# zif_socket.net
KiCad netlist of a schematic drawn in EAGLE
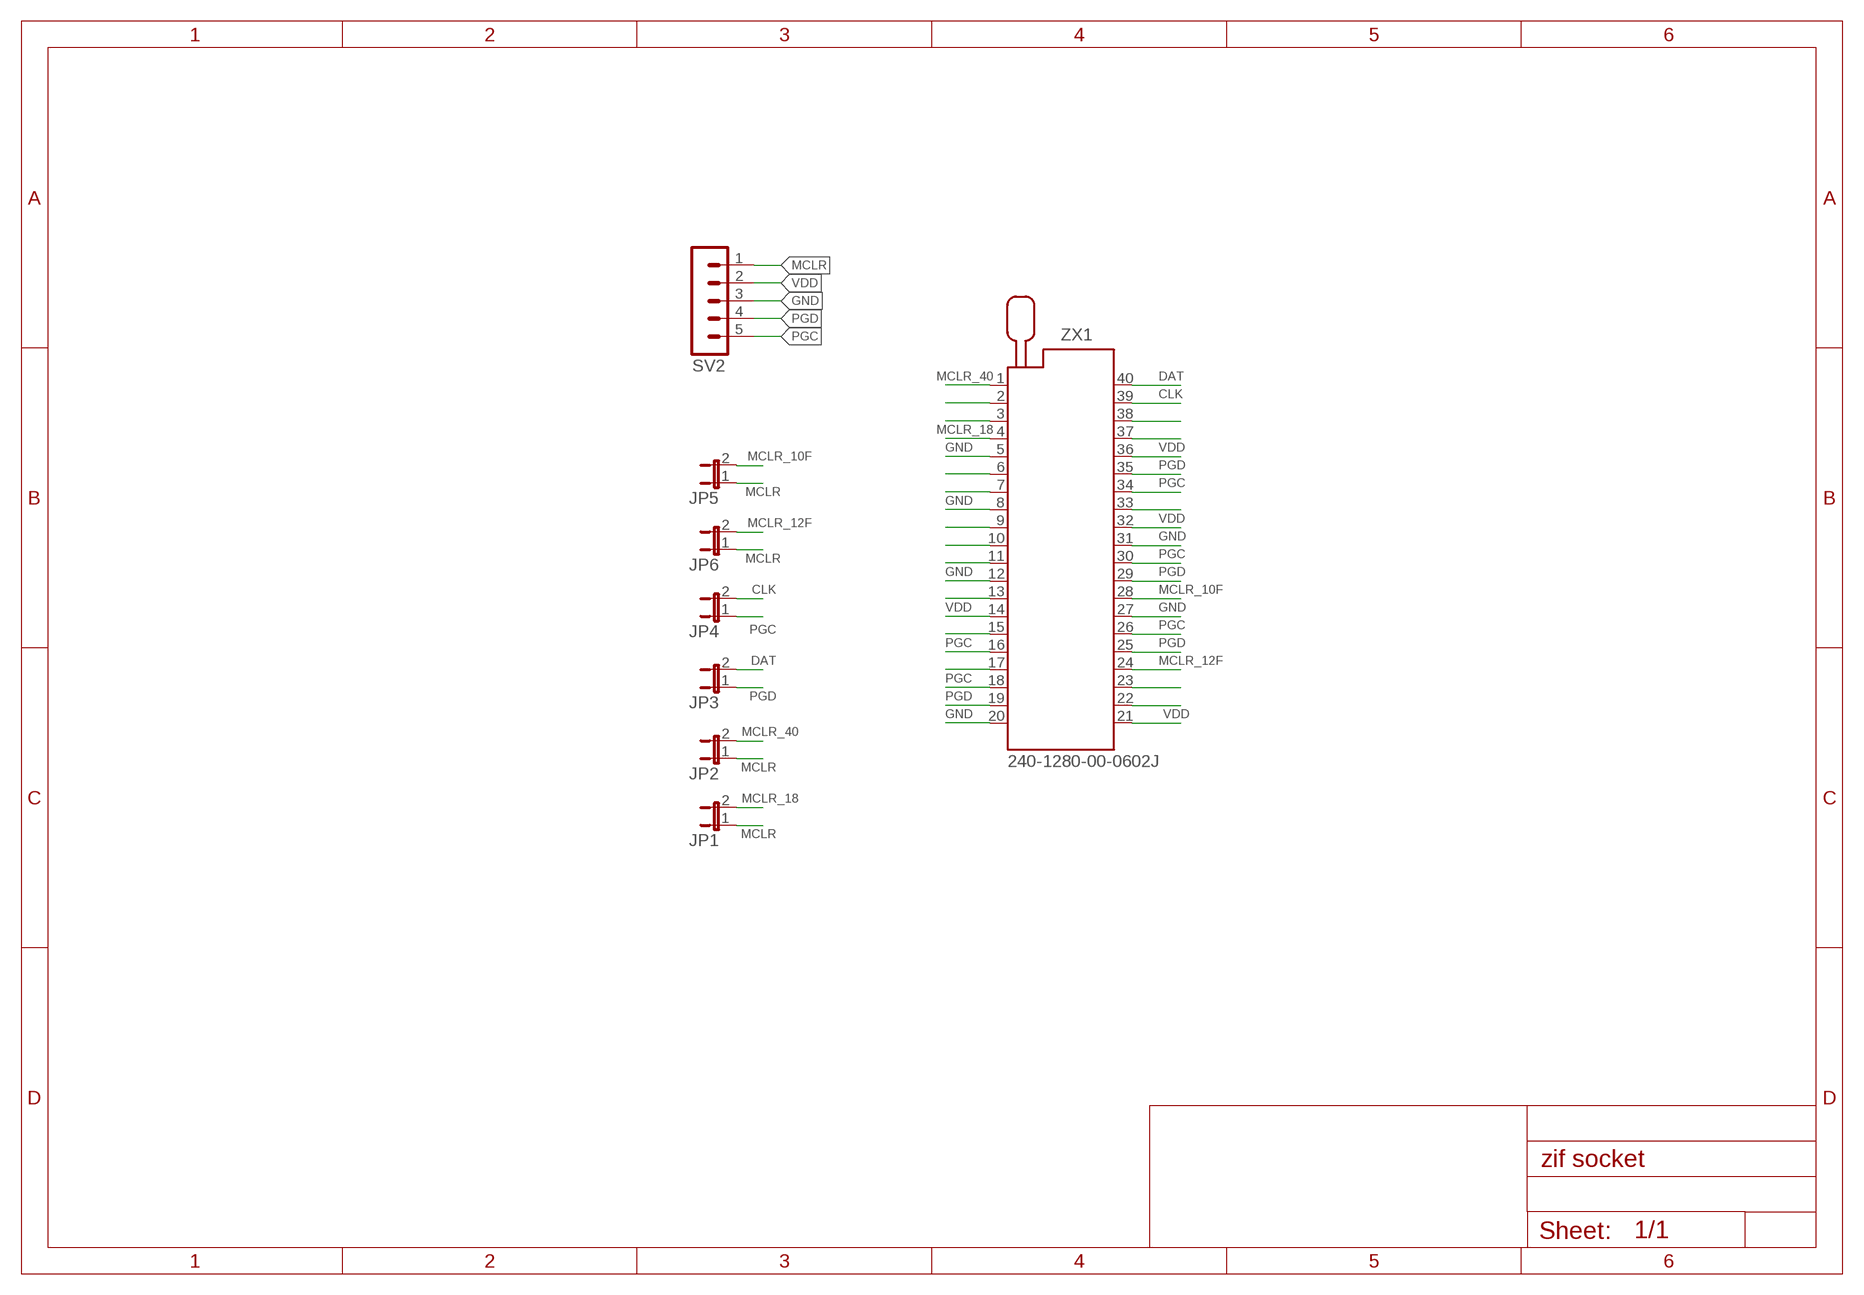
[diagram p0: schematic, sheet 1]

(export (version "E")
  (design (tool "Eeschema 10.0.6"))
  (components
    (comp (ref "JP1")
      (value "JP1E")
      (footprint "eagle-import:JP1")
      (libsource (lib "eagle-import") (part "JP1E"))
    )
    (comp (ref "JP2")
      (value "JP1E")
      (footprint "eagle-import:JP1")
      (libsource (lib "eagle-import") (part "JP1E"))
    )
    (comp (ref "JP3")
      (value "JP1E")
      (footprint "eagle-import:JP1")
      (libsource (lib "eagle-import") (part "JP1E"))
    )
    (comp (ref "JP4")
      (value "JP1E")
      (footprint "eagle-import:JP1")
      (libsource (lib "eagle-import") (part "JP1E"))
    )
    (comp (ref "JP5")
      (value "JP1E")
      (footprint "eagle-import:JP1")
      (libsource (lib "eagle-import") (part "JP1E"))
    )
    (comp (ref "JP6")
      (value "JP1E")
      (footprint "eagle-import:JP1")
      (libsource (lib "eagle-import") (part "JP1E"))
    )
    (comp (ref "SV2")
      (value "MA05-1")
      (footprint "eagle-import:MA05-1")
      (libsource (lib "eagle-import") (part "MA05-1"))
    )
    (comp (ref "ZX1")
      (value "240-1280-00-0602J")
      (footprint "eagle-import:240-1280-00-0602J")
      (libsource (lib "eagle-import") (part "240-?-00-0602J1280"))
    )
  )
  (nets
    (net (code "1") (name "/CLK") (class "Default")
      (node (ref "JP4") (pin "2") (pinfunction "2_2") (pintype "passive"))
      (node (ref "ZX1") (pin "39") (pinfunction "39_39") (pintype "passive"))
    )
    (net (code "2") (name "/DAT") (class "Default")
      (node (ref "JP3") (pin "2") (pinfunction "2_2") (pintype "passive"))
      (node (ref "ZX1") (pin "40") (pinfunction "40_40") (pintype "passive"))
    )
    (net (code "3") (name "/MCLR_10F") (class "Default")
      (node (ref "JP5") (pin "2") (pinfunction "2_2") (pintype "passive"))
      (node (ref "ZX1") (pin "28") (pinfunction "28_28") (pintype "passive"))
    )
    (net (code "4") (name "/MCLR_12F") (class "Default")
      (node (ref "JP6") (pin "2") (pinfunction "2_2") (pintype "passive"))
      (node (ref "ZX1") (pin "24") (pinfunction "24_24") (pintype "passive"))
    )
    (net (code "5") (name "/MCLR_18") (class "Default")
      (node (ref "JP1") (pin "2") (pinfunction "2_2") (pintype "passive"))
      (node (ref "ZX1") (pin "4") (pinfunction "4_4") (pintype "passive"))
    )
    (net (code "6") (name "/MCLR_40") (class "Default")
      (node (ref "JP2") (pin "2") (pinfunction "2_2") (pintype "passive"))
      (node (ref "ZX1") (pin "1") (pinfunction "1_1") (pintype "passive"))
    )
    (net (code "7") (name "GND") (class "Default")
      (node (ref "SV2") (pin "3") (pinfunction "3_3") (pintype "passive"))
      (node (ref "ZX1") (pin "12") (pinfunction "12_12") (pintype "passive"))
      (node (ref "ZX1") (pin "20") (pinfunction "20_20") (pintype "passive"))
      (node (ref "ZX1") (pin "27") (pinfunction "27_27") (pintype "passive"))
      (node (ref "ZX1") (pin "31") (pinfunction "31_31") (pintype "passive"))
      (node (ref "ZX1") (pin "5") (pinfunction "5_5") (pintype "passive"))
      (node (ref "ZX1") (pin "8") (pinfunction "8_8") (pintype "passive"))
    )
    (net (code "8") (name "MCLR") (class "Default")
      (node (ref "JP1") (pin "1") (pinfunction "1_1") (pintype "passive"))
      (node (ref "JP2") (pin "1") (pinfunction "1_1") (pintype "passive"))
      (node (ref "JP5") (pin "1") (pinfunction "1_1") (pintype "passive"))
      (node (ref "JP6") (pin "1") (pinfunction "1_1") (pintype "passive"))
      (node (ref "SV2") (pin "1") (pinfunction "1_1") (pintype "passive"))
    )
    (net (code "9") (name "PGC") (class "Default")
      (node (ref "JP4") (pin "1") (pinfunction "1_1") (pintype "passive"))
      (node (ref "SV2") (pin "5") (pinfunction "5_5") (pintype "passive"))
      (node (ref "ZX1") (pin "16") (pinfunction "16_16") (pintype "passive"))
      (node (ref "ZX1") (pin "18") (pinfunction "18_18") (pintype "passive"))
      (node (ref "ZX1") (pin "26") (pinfunction "26_26") (pintype "passive"))
      (node (ref "ZX1") (pin "30") (pinfunction "30_30") (pintype "passive"))
      (node (ref "ZX1") (pin "34") (pinfunction "34_34") (pintype "passive"))
    )
    (net (code "10") (name "PGD") (class "Default")
      (node (ref "JP3") (pin "1") (pinfunction "1_1") (pintype "passive"))
      (node (ref "SV2") (pin "4") (pinfunction "4_4") (pintype "passive"))
      (node (ref "ZX1") (pin "19") (pinfunction "19_19") (pintype "passive"))
      (node (ref "ZX1") (pin "25") (pinfunction "25_25") (pintype "passive"))
      (node (ref "ZX1") (pin "29") (pinfunction "29_29") (pintype "passive"))
      (node (ref "ZX1") (pin "35") (pinfunction "35_35") (pintype "passive"))
    )
    (net (code "11") (name "VDD") (class "Default")
      (node (ref "SV2") (pin "2") (pinfunction "2_2") (pintype "passive"))
      (node (ref "ZX1") (pin "14") (pinfunction "14_14") (pintype "passive"))
      (node (ref "ZX1") (pin "21") (pinfunction "21_21") (pintype "passive"))
      (node (ref "ZX1") (pin "32") (pinfunction "32_32") (pintype "passive"))
      (node (ref "ZX1") (pin "36") (pinfunction "36_36") (pintype "passive"))
    )
    (net (code "12") (name "unconnected-(ZX1-Pad2)") (class "Default")
      (node (ref "ZX1") (pin "2") (pinfunction "2_2") (pintype "passive"))
    )
    (net (code "13") (name "unconnected-(ZX1-Pad3)") (class "Default")
      (node (ref "ZX1") (pin "3") (pinfunction "3_3") (pintype "passive"))
    )
    (net (code "14") (name "unconnected-(ZX1-Pad6)") (class "Default")
      (node (ref "ZX1") (pin "6") (pinfunction "6_6") (pintype "passive"))
    )
    (net (code "15") (name "unconnected-(ZX1-Pad7)") (class "Default")
      (node (ref "ZX1") (pin "7") (pinfunction "7_7") (pintype "passive"))
    )
    (net (code "16") (name "unconnected-(ZX1-Pad9)") (class "Default")
      (node (ref "ZX1") (pin "9") (pinfunction "9_9") (pintype "passive"))
    )
    (net (code "17") (name "unconnected-(ZX1-Pad10)") (class "Default")
      (node (ref "ZX1") (pin "10") (pinfunction "10_10") (pintype "passive"))
    )
    (net (code "18") (name "unconnected-(ZX1-Pad11)") (class "Default")
      (node (ref "ZX1") (pin "11") (pinfunction "11_11") (pintype "passive"))
    )
    (net (code "19") (name "unconnected-(ZX1-Pad13)") (class "Default")
      (node (ref "ZX1") (pin "13") (pinfunction "13_13") (pintype "passive"))
    )
    (net (code "20") (name "unconnected-(ZX1-Pad15)") (class "Default")
      (node (ref "ZX1") (pin "15") (pinfunction "15_15") (pintype "passive"))
    )
    (net (code "21") (name "unconnected-(ZX1-Pad17)") (class "Default")
      (node (ref "ZX1") (pin "17") (pinfunction "17_17") (pintype "passive"))
    )
    (net (code "22") (name "unconnected-(ZX1-Pad22)") (class "Default")
      (node (ref "ZX1") (pin "22") (pinfunction "22_22") (pintype "passive"))
    )
    (net (code "23") (name "unconnected-(ZX1-Pad23)") (class "Default")
      (node (ref "ZX1") (pin "23") (pinfunction "23_23") (pintype "passive"))
    )
    (net (code "24") (name "unconnected-(ZX1-Pad33)") (class "Default")
      (node (ref "ZX1") (pin "33") (pinfunction "33_33") (pintype "passive"))
    )
    (net (code "25") (name "unconnected-(ZX1-Pad37)") (class "Default")
      (node (ref "ZX1") (pin "37") (pinfunction "37_37") (pintype "passive"))
    )
    (net (code "26") (name "unconnected-(ZX1-Pad38)") (class "Default")
      (node (ref "ZX1") (pin "38") (pinfunction "38_38") (pintype "passive"))
    )
  )
)
